# Module_T_H_03v.net
KiCad netlist of a schematic drawn in EAGLE
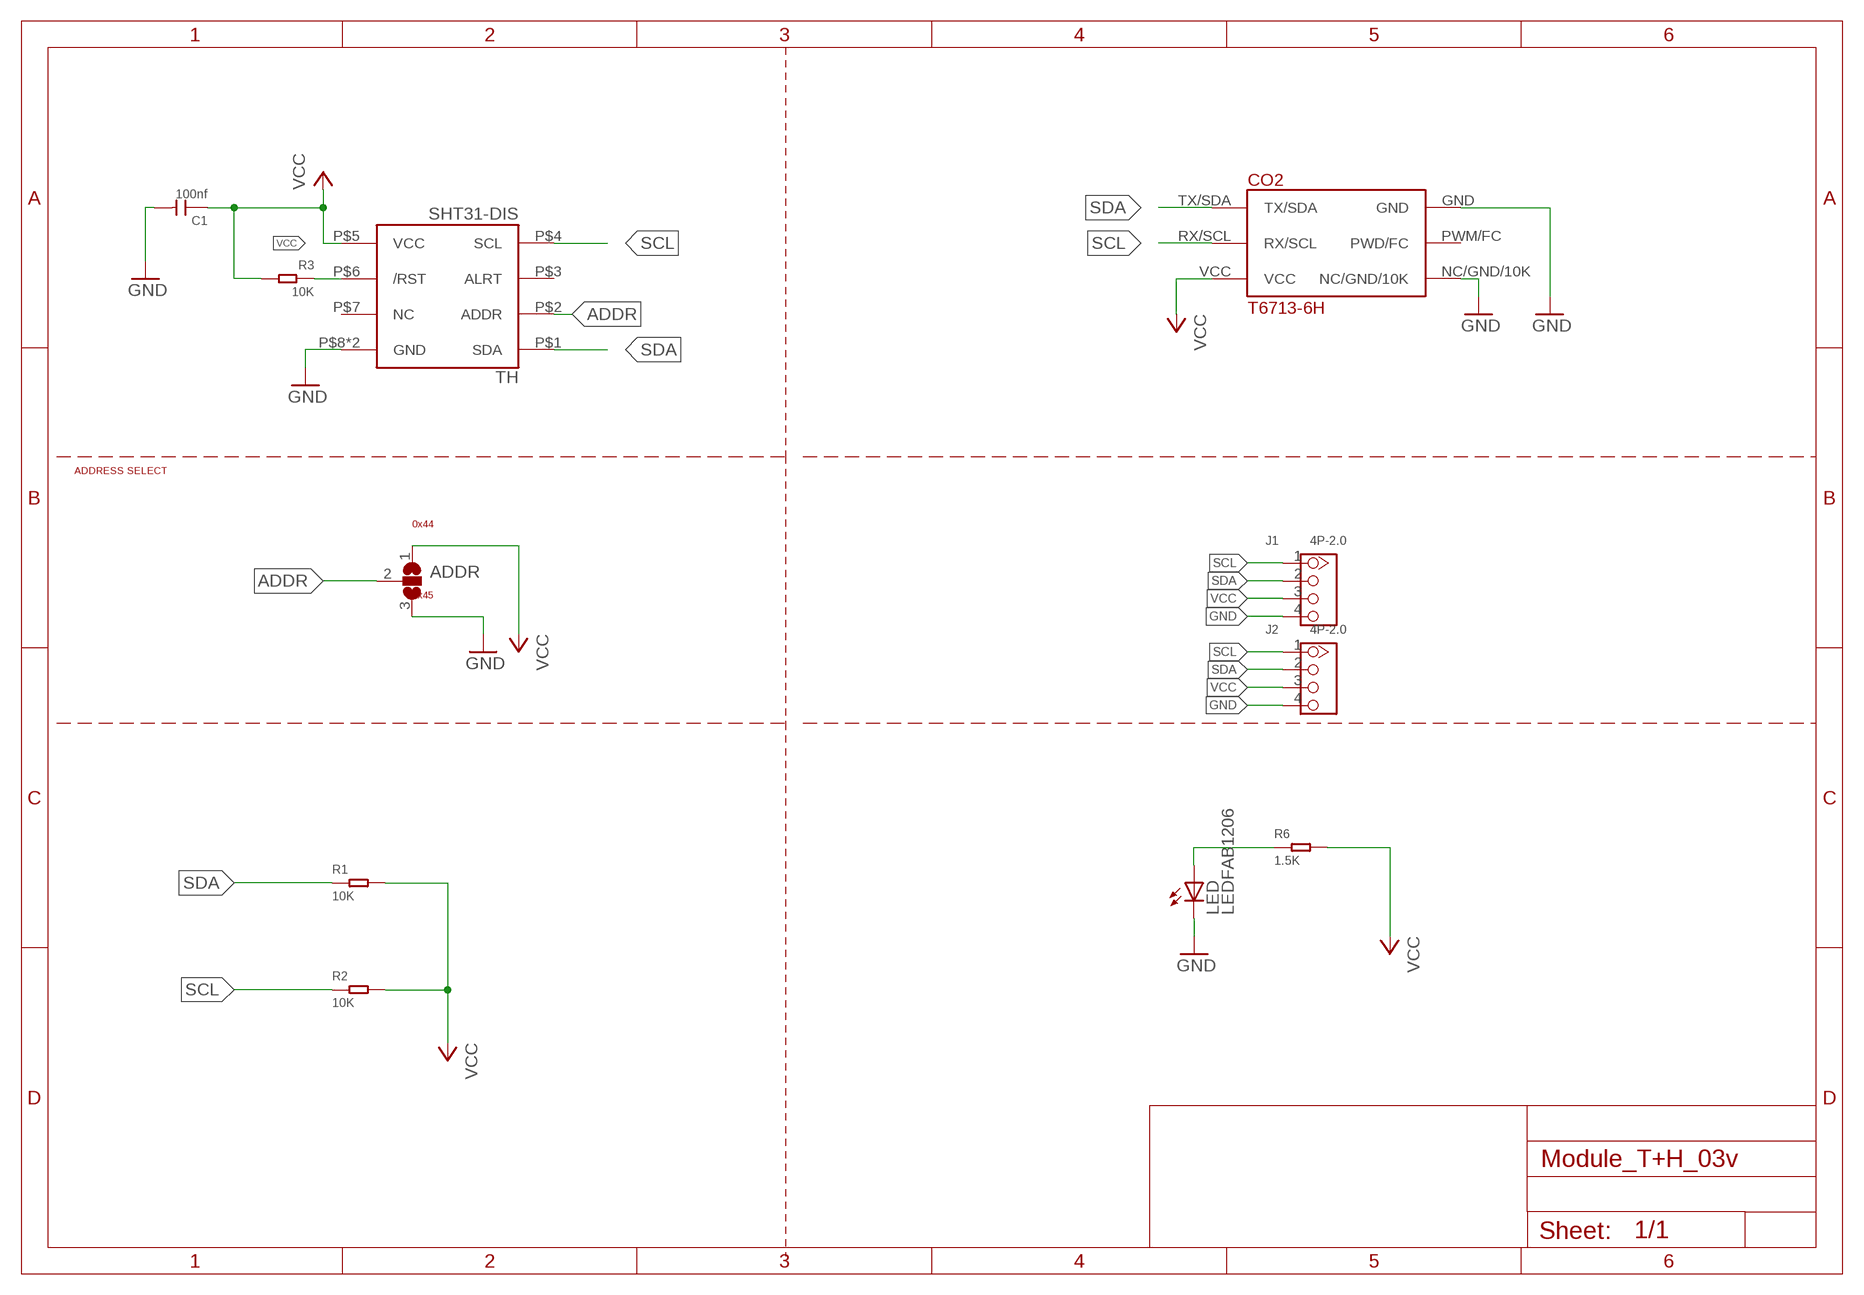
[diagram p0: schematic, sheet 1]

(export (version "E")
  (design (tool "Eeschema 10.0.6"))
  (components
    (comp (ref "ADDR")
      (value "SJ2W")
      (footprint "eagle-import:SJ_2")
      (libsource (lib "eagle-import") (part "SJ2W"))
    )
    (comp (ref "C1")
      (value "100nf")
      (footprint "eagle-import:C0805")
      (fields (field (name "MPN") "CC0805KRX7R9BB104"))
      (libsource (lib "eagle-import") (part "CERAMIC-100NF-50V-10%-X7R(0805)"))
    )
    (comp (ref "CO2")
      (value "T6713-6H")
      (footprint "eagle-import:PINS")
      (libsource (lib "eagle-import") (part "T6713-6H"))
    )
    (comp (ref "J1")
      (value "4P-2.0")
      (footprint "eagle-import:HW4-2.0")
      (libsource (lib "eagle-import") (part "GROVE-CONNECTOR-DIP(4P-2.0)"))
    )
    (comp (ref "J2")
      (value "4P-2.0")
      (footprint "eagle-import:HW4-2.0")
      (libsource (lib "eagle-import") (part "GROVE-CONNECTOR-DIP(4P-2.0)"))
    )
    (comp (ref "LED")
      (value "LEDFAB1206")
      (footprint "eagle-import:LED1206FAB")
      (libsource (lib "eagle-import") (part "LEDFAB1206"))
    )
    (comp (ref "R1")
      (value "10K")
      (footprint "eagle-import:R0805")
      (fields (field (name "MPN") "RC0805FR-0710KL"))
      (libsource (lib "eagle-import") (part "SMD-RES-10K-1%-1/8W(0805)"))
    )
    (comp (ref "R2")
      (value "10K")
      (footprint "eagle-import:R0805")
      (fields (field (name "MPN") "RC0805FR-0710KL"))
      (libsource (lib "eagle-import") (part "SMD-RES-10K-1%-1/8W(0805)"))
    )
    (comp (ref "R3")
      (value "10K")
      (footprint "eagle-import:R0805")
      (fields (field (name "MPN") "RC0805FR-0710KL"))
      (libsource (lib "eagle-import") (part "SMD-RES-10K-1%-1/8W(0805)"))
    )
    (comp (ref "R6")
      (value "1.5K")
      (footprint "eagle-import:R0805")
      (fields (field (name "MPN") "RC0805FR-071K5L"))
      (libsource (lib "eagle-import") (part "SMD-RES-1.5K-1%-1/8W(0805)"))
    )
    (comp (ref "TH")
      (value "SHT31-DIS")
      (footprint "eagle-import:SHT3X")
      (libsource (lib "eagle-import") (part "SHT31-DIS"))
    )
  )
  (nets
    (net (code "1") (name "ADDR") (class "Default")
      (node (ref "ADDR") (pin "2") (pinfunction "2_2") (pintype "passive"))
      (node (ref "TH") (pin "P$2") (pinfunction "ADDR_P$2") (pintype "bidirectional"))
    )
    (net (code "2") (name "GND") (class "Default")
      (node (ref "ADDR") (pin "3") (pinfunction "3_3") (pintype "passive"))
      (node (ref "C1") (pin "2") (pinfunction "2_2") (pintype "passive"))
      (node (ref "CO2") (pin "GND") (pinfunction "GND_GND") (pintype "bidirectional"))
      (node (ref "CO2") (pin "NC/GND/10K") (pinfunction "NC/GND/10K_NC/GND/10K") (pintype "bidirectional"))
      (node (ref "J1") (pin "4") (pinfunction "4_4") (pintype "bidirectional"))
      (node (ref "J2") (pin "4") (pinfunction "4_4") (pintype "bidirectional"))
      (node (ref "LED") (pin "2") (pinfunction "C_2") (pintype "passive"))
      (node (ref "TH") (pin "P$8") (pinfunction "GND_P$8") (pintype "bidirectional"))
      (node (ref "TH") (pin "PAD") (pinfunction "GND_PAD") (pintype "bidirectional"))
    )
    (net (code "3") (name "Net-(LED-A)") (class "Default")
      (node (ref "LED") (pin "1") (pinfunction "A_1") (pintype "passive"))
      (node (ref "R6") (pin "1") (pinfunction "1_1") (pintype "passive"))
    )
    (net (code "4") (name "Net-(TH-{slash}RST)") (class "Default")
      (node (ref "R3") (pin "1") (pinfunction "1_1") (pintype "passive"))
      (node (ref "TH") (pin "P$6") (pinfunction "/RST_P$6") (pintype "bidirectional"))
    )
    (net (code "5") (name "SCL") (class "Default")
      (node (ref "CO2") (pin "RX/SCL") (pinfunction "RX/SCL_RX/SCL") (pintype "bidirectional"))
      (node (ref "J1") (pin "1") (pinfunction "1_1") (pintype "bidirectional"))
      (node (ref "J2") (pin "1") (pinfunction "1_1") (pintype "bidirectional"))
      (node (ref "R2") (pin "1") (pinfunction "1_1") (pintype "passive"))
      (node (ref "TH") (pin "P$4") (pinfunction "SCL_P$4") (pintype "bidirectional"))
    )
    (net (code "6") (name "SDA") (class "Default")
      (node (ref "CO2") (pin "TX/SDA") (pinfunction "TX/SDA_TX/SDA") (pintype "bidirectional"))
      (node (ref "J1") (pin "2") (pinfunction "2_2") (pintype "bidirectional"))
      (node (ref "J2") (pin "2") (pinfunction "2_2") (pintype "bidirectional"))
      (node (ref "R1") (pin "1") (pinfunction "1_1") (pintype "passive"))
      (node (ref "TH") (pin "P$1") (pinfunction "SDA_P$1") (pintype "bidirectional"))
    )
    (net (code "7") (name "VCC") (class "Default")
      (node (ref "ADDR") (pin "1") (pinfunction "1_1") (pintype "passive"))
      (node (ref "C1") (pin "1") (pinfunction "1_1") (pintype "passive"))
      (node (ref "CO2") (pin "VCC") (pinfunction "VCC_VCC") (pintype "bidirectional"))
      (node (ref "J1") (pin "3") (pinfunction "3_3") (pintype "bidirectional"))
      (node (ref "J2") (pin "3") (pinfunction "3_3") (pintype "bidirectional"))
      (node (ref "R1") (pin "2") (pinfunction "2_2") (pintype "passive"))
      (node (ref "R2") (pin "2") (pinfunction "2_2") (pintype "passive"))
      (node (ref "R3") (pin "2") (pinfunction "2_2") (pintype "passive"))
      (node (ref "R6") (pin "2") (pinfunction "2_2") (pintype "passive"))
      (node (ref "TH") (pin "P$5") (pinfunction "VCC_P$5") (pintype "bidirectional"))
    )
    (net (code "8") (name "unconnected-(CO2-PWD{slash}FC-PadPWM{slash}FC)") (class "Default")
      (node (ref "CO2") (pin "PWM/FC") (pinfunction "PWD/FC_PWM/FC") (pintype "bidirectional"))
    )
    (net (code "9") (name "unconnected-(TH-ALRT-PadP$3)") (class "Default")
      (node (ref "TH") (pin "P$3") (pinfunction "ALRT_P$3") (pintype "bidirectional"))
    )
    (net (code "10") (name "unconnected-(TH-NC-PadP$7)") (class "Default")
      (node (ref "TH") (pin "P$7") (pinfunction "NC_P$7") (pintype "bidirectional"))
    )
  )
)
